# SLIM-DDS-107.net
KiCad netlist of a schematic drawn in EAGLE
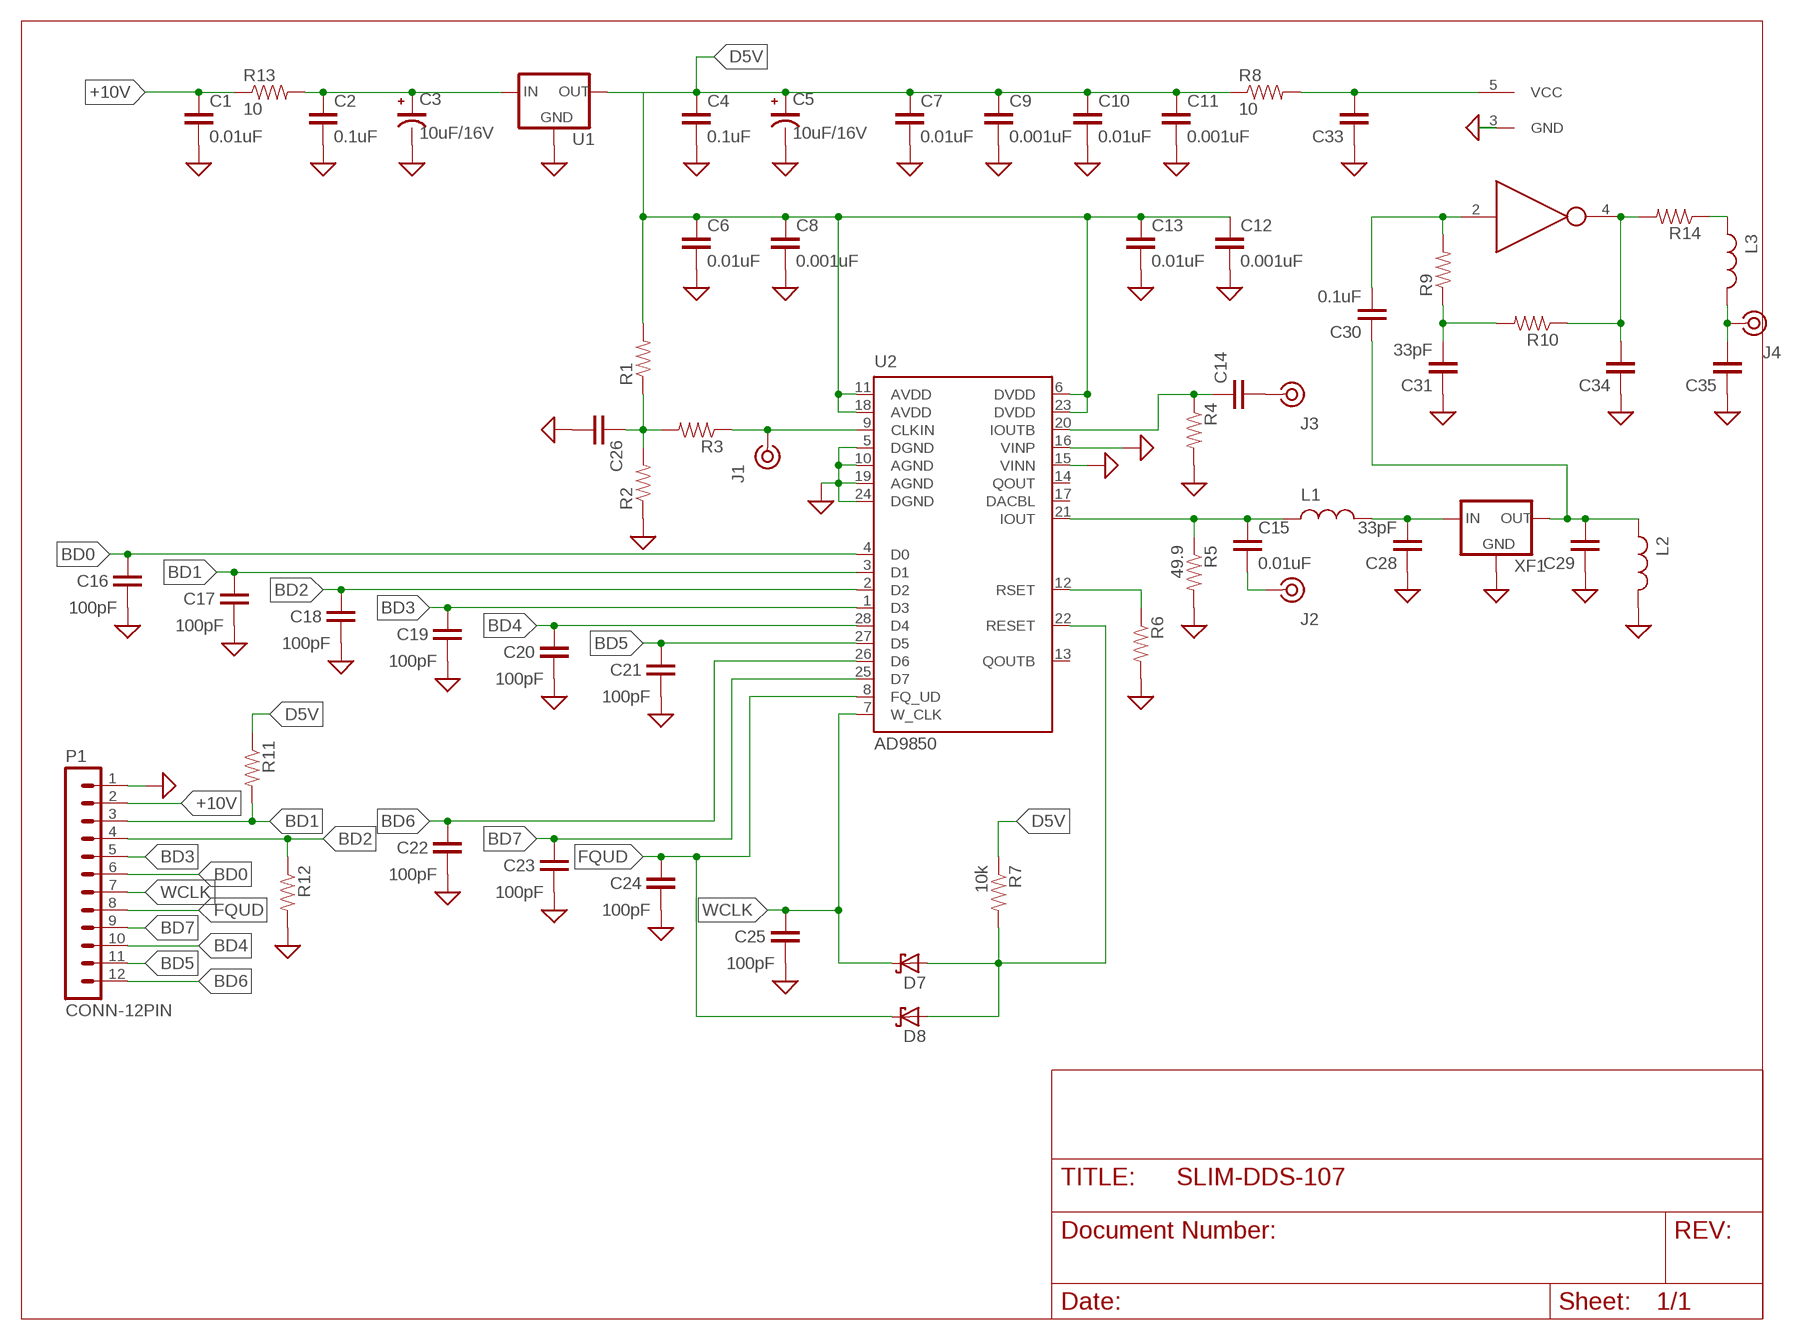
[diagram p0: schematic, sheet 1]

(export (version "E")
  (design (tool "Eeschema 10.0.6"))
  (components
    (comp (ref "C1")
      (value "0.01uF")
      (footprint "eagle-import:0805")
      (libsource (lib "eagle-import") (part "CAP0805"))
    )
    (comp (ref "C2")
      (value "0.1uF")
      (footprint "eagle-import:0805")
      (libsource (lib "eagle-import") (part "CAP0805"))
    )
    (comp (ref "C3")
      (value "10uF/16V")
      (footprint "eagle-import:EIA3216")
      (libsource (lib "eagle-import") (part "CAP-POL1206"))
    )
    (comp (ref "C4")
      (value "0.1uF")
      (footprint "eagle-import:0805")
      (libsource (lib "eagle-import") (part "CAP0805"))
    )
    (comp (ref "C5")
      (value "10uF/16V")
      (footprint "eagle-import:EIA3216")
      (libsource (lib "eagle-import") (part "CAP-POL1206"))
    )
    (comp (ref "C6")
      (value "0.01uF")
      (footprint "eagle-import:0805")
      (libsource (lib "eagle-import") (part "CAP0805"))
    )
    (comp (ref "C7")
      (value "0.01uF")
      (footprint "eagle-import:0805")
      (libsource (lib "eagle-import") (part "CAP0805"))
    )
    (comp (ref "C8")
      (value "0.001uF")
      (footprint "eagle-import:0805")
      (libsource (lib "eagle-import") (part "CAP0805"))
    )
    (comp (ref "C9")
      (value "0.001uF")
      (footprint "eagle-import:0805")
      (libsource (lib "eagle-import") (part "CAP0805"))
    )
    (comp (ref "C10")
      (value "0.01uF")
      (footprint "eagle-import:0805")
      (libsource (lib "eagle-import") (part "CAP0805"))
    )
    (comp (ref "C11")
      (value "0.001uF")
      (footprint "eagle-import:0805")
      (libsource (lib "eagle-import") (part "CAP0805"))
    )
    (comp (ref "C12")
      (value "0.001uF")
      (footprint "eagle-import:0805")
      (libsource (lib "eagle-import") (part "CAP0805"))
    )
    (comp (ref "C13")
      (value "0.01uF")
      (footprint "eagle-import:0805")
      (libsource (lib "eagle-import") (part "CAP0805"))
    )
    (comp (ref "C14")
      (value "CAP0805")
      (footprint "eagle-import:0805")
      (libsource (lib "eagle-import") (part "CAP0805"))
    )
    (comp (ref "C15")
      (value "0.01uF")
      (footprint "eagle-import:0805")
      (libsource (lib "eagle-import") (part "CAP0805"))
    )
    (comp (ref "C16")
      (value "100pF")
      (footprint "eagle-import:0805")
      (libsource (lib "eagle-import") (part "CAP0805"))
    )
    (comp (ref "C17")
      (value "100pF")
      (footprint "eagle-import:0805")
      (libsource (lib "eagle-import") (part "CAP0805"))
    )
    (comp (ref "C18")
      (value "100pF")
      (footprint "eagle-import:0805")
      (libsource (lib "eagle-import") (part "CAP0805"))
    )
    (comp (ref "C19")
      (value "100pF")
      (footprint "eagle-import:0805")
      (libsource (lib "eagle-import") (part "CAP0805"))
    )
    (comp (ref "C20")
      (value "100pF")
      (footprint "eagle-import:0805")
      (libsource (lib "eagle-import") (part "CAP0805"))
    )
    (comp (ref "C21")
      (value "100pF")
      (footprint "eagle-import:0805")
      (libsource (lib "eagle-import") (part "CAP0805"))
    )
    (comp (ref "C22")
      (value "100pF")
      (footprint "eagle-import:0805")
      (libsource (lib "eagle-import") (part "CAP0805"))
    )
    (comp (ref "C23")
      (value "100pF")
      (footprint "eagle-import:0805")
      (libsource (lib "eagle-import") (part "CAP0805"))
    )
    (comp (ref "C24")
      (value "100pF")
      (footprint "eagle-import:0805")
      (libsource (lib "eagle-import") (part "CAP0805"))
    )
    (comp (ref "C25")
      (value "100pF")
      (footprint "eagle-import:0805")
      (libsource (lib "eagle-import") (part "CAP0805"))
    )
    (comp (ref "C26")
      (value "CAP0805")
      (footprint "eagle-import:0805")
      (libsource (lib "eagle-import") (part "CAP0805"))
    )
    (comp (ref "C28")
      (value "33pF")
      (footprint "eagle-import:0805")
      (libsource (lib "eagle-import") (part "CAP0805"))
    )
    (comp (ref "C29")
      (value "CAP0805")
      (footprint "eagle-import:0805")
      (libsource (lib "eagle-import") (part "CAP0805"))
    )
    (comp (ref "C30")
      (value "0.1uF")
      (footprint "eagle-import:0805")
      (libsource (lib "eagle-import") (part "CAP0805"))
    )
    (comp (ref "C31")
      (value "33pF")
      (footprint "eagle-import:0805")
      (libsource (lib "eagle-import") (part "CAP0805"))
    )
    (comp (ref "C33")
      (value "CAP0805")
      (footprint "eagle-import:0805")
      (libsource (lib "eagle-import") (part "CAP0805"))
    )
    (comp (ref "C34")
      (value "CAP0805")
      (footprint "eagle-import:0805")
      (libsource (lib "eagle-import") (part "CAP0805"))
    )
    (comp (ref "C35")
      (value "CAP0805")
      (footprint "eagle-import:0805")
      (libsource (lib "eagle-import") (part "CAP0805"))
    )
    (comp (ref "D7")
      (value "SCHOTTKY-DIODE-SOD323")
      (footprint "eagle-import:SOD323")
      (libsource (lib "eagle-import") (part "SCHOTTKY-DIODE-SOD323"))
    )
    (comp (ref "D8")
      (value "SCHOTTKY-DIODE-SOD323")
      (footprint "eagle-import:SOD323")
      (libsource (lib "eagle-import") (part "SCHOTTKY-DIODE-SOD323"))
    )
    (comp (ref "J1")
      (value "COAX")
      (footprint "eagle-import:SLIM_COAX_PAD")
      (libsource (lib "eagle-import") (part "COAX"))
    )
    (comp (ref "J2")
      (value "COAX")
      (footprint "eagle-import:SLIM_COAX_PAD")
      (libsource (lib "eagle-import") (part "COAX"))
    )
    (comp (ref "J3")
      (value "COAX")
      (footprint "eagle-import:SLIM_COAX_PAD")
      (libsource (lib "eagle-import") (part "COAX"))
    )
    (comp (ref "J4")
      (value "COAX")
      (footprint "eagle-import:SLIM_COAX_PAD")
      (libsource (lib "eagle-import") (part "COAX"))
    )
    (comp (ref "L1")
      (value "INDUCTOR0805")
      (footprint "eagle-import:0805-IND")
      (libsource (lib "eagle-import") (part "INDUCTOR0805"))
    )
    (comp (ref "L2")
      (value "INDUCTOR0805")
      (footprint "eagle-import:0805-IND")
      (libsource (lib "eagle-import") (part "INDUCTOR0805"))
    )
    (comp (ref "L3")
      (value "INDUCTOR0805")
      (footprint "eagle-import:0805-IND")
      (libsource (lib "eagle-import") (part "INDUCTOR0805"))
    )
    (comp (ref "P1")
      (value "CONN-12PIN")
      (footprint "eagle-import:CONN-12PIN")
      (libsource (lib "eagle-import") (part "CONN-12PIN"))
    )
    (comp (ref "R1")
      (value "RESISTOR0805")
      (footprint "eagle-import:0805")
      (libsource (lib "eagle-import") (part "RESISTOR0805"))
    )
    (comp (ref "R2")
      (value "RESISTOR0805")
      (footprint "eagle-import:0805")
      (libsource (lib "eagle-import") (part "RESISTOR0805"))
    )
    (comp (ref "R3")
      (value "RESISTOR0805")
      (footprint "eagle-import:0805")
      (libsource (lib "eagle-import") (part "RESISTOR0805"))
    )
    (comp (ref "R4")
      (value "RESISTOR0805")
      (footprint "eagle-import:0805")
      (libsource (lib "eagle-import") (part "RESISTOR0805"))
    )
    (comp (ref "R5")
      (value "49.9")
      (footprint "eagle-import:0805")
      (libsource (lib "eagle-import") (part "RESISTOR0805"))
    )
    (comp (ref "R6")
      (value "RESISTOR0805")
      (footprint "eagle-import:0805")
      (libsource (lib "eagle-import") (part "RESISTOR0805"))
    )
    (comp (ref "R7")
      (value "10k")
      (footprint "eagle-import:0805")
      (libsource (lib "eagle-import") (part "RESISTOR0805"))
    )
    (comp (ref "R8")
      (value "10")
      (footprint "eagle-import:0805")
      (libsource (lib "eagle-import") (part "RESISTOR0805"))
    )
    (comp (ref "R9")
      (value "RESISTOR0805")
      (footprint "eagle-import:0805")
      (libsource (lib "eagle-import") (part "RESISTOR0805"))
    )
    (comp (ref "R10")
      (value "RESISTOR0805")
      (footprint "eagle-import:0805")
      (libsource (lib "eagle-import") (part "RESISTOR0805"))
    )
    (comp (ref "R11")
      (value "RESISTOR0805")
      (footprint "eagle-import:0805")
      (libsource (lib "eagle-import") (part "RESISTOR0805"))
    )
    (comp (ref "R12")
      (value "RESISTOR0805")
      (footprint "eagle-import:0805")
      (libsource (lib "eagle-import") (part "RESISTOR0805"))
    )
    (comp (ref "R13")
      (value "10")
      (footprint "eagle-import:0805")
      (libsource (lib "eagle-import") (part "RESISTOR0805"))
    )
    (comp (ref "R14")
      (value "RESISTOR0805")
      (footprint "eagle-import:0805")
      (libsource (lib "eagle-import") (part "RESISTOR0805"))
    )
    (comp (ref "U$1")
      (value "7SZ04SOT-23")
      (footprint "eagle-import:SOT23-5L")
      (libsource (lib "eagle-import") (part "7SZ04SOT-23"))
    )
    (comp (ref "U1")
      (value "78MXXLDPAK")
      (footprint "eagle-import:TO252")
      (libsource (lib "eagle-import") (part "78MXXLDPAK"))
    )
    (comp (ref "U2")
      (value "AD9850")
      (footprint "eagle-import:SSOP28")
      (libsource (lib "eagle-import") (part "AD9850"))
    )
    (comp (ref "XF1")
      (value "XTALFILTER")
      (footprint "eagle-import:XTALFILTER")
      (libsource (lib "eagle-import") (part "XTALFILTER"))
    )
  )
  (nets
    (net (code "1") (name "+10V") (class "Default")
      (node (ref "C1") (pin "1") (pinfunction "1_1") (pintype "passive"))
      (node (ref "P1") (pin "2") (pinfunction "2_2") (pintype "passive"))
      (node (ref "R13") (pin "1") (pinfunction "1_1") (pintype "passive"))
    )
    (net (code "2") (name "BD0") (class "Default")
      (node (ref "C16") (pin "2") (pinfunction "2_2") (pintype "passive"))
      (node (ref "P1") (pin "6") (pinfunction "6_6") (pintype "passive"))
      (node (ref "U2") (pin "4") (pinfunction "D0_4") (pintype "bidirectional"))
    )
    (net (code "3") (name "BD1") (class "Default")
      (node (ref "C17") (pin "2") (pinfunction "2_2") (pintype "passive"))
      (node (ref "P1") (pin "3") (pinfunction "3_3") (pintype "passive"))
      (node (ref "R11") (pin "2") (pinfunction "2_2") (pintype "passive"))
      (node (ref "U2") (pin "3") (pinfunction "D1_3") (pintype "bidirectional"))
    )
    (net (code "4") (name "BD2") (class "Default")
      (node (ref "C18") (pin "2") (pinfunction "2_2") (pintype "passive"))
      (node (ref "P1") (pin "4") (pinfunction "4_4") (pintype "passive"))
      (node (ref "R12") (pin "1") (pinfunction "1_1") (pintype "passive"))
      (node (ref "U2") (pin "2") (pinfunction "D2_2") (pintype "bidirectional"))
    )
    (net (code "5") (name "BD3") (class "Default")
      (node (ref "C19") (pin "2") (pinfunction "2_2") (pintype "passive"))
      (node (ref "P1") (pin "5") (pinfunction "5_5") (pintype "passive"))
      (node (ref "U2") (pin "1") (pinfunction "D3_1") (pintype "bidirectional"))
    )
    (net (code "6") (name "BD4") (class "Default")
      (node (ref "C20") (pin "2") (pinfunction "2_2") (pintype "passive"))
      (node (ref "P1") (pin "10") (pinfunction "10_10") (pintype "passive"))
      (node (ref "U2") (pin "28") (pinfunction "D4_28") (pintype "bidirectional"))
    )
    (net (code "7") (name "BD5") (class "Default")
      (node (ref "C21") (pin "2") (pinfunction "2_2") (pintype "passive"))
      (node (ref "P1") (pin "11") (pinfunction "11_11") (pintype "passive"))
      (node (ref "U2") (pin "27") (pinfunction "D5_27") (pintype "bidirectional"))
    )
    (net (code "8") (name "BD6") (class "Default")
      (node (ref "C22") (pin "2") (pinfunction "2_2") (pintype "passive"))
      (node (ref "P1") (pin "12") (pinfunction "12_12") (pintype "passive"))
      (node (ref "U2") (pin "26") (pinfunction "D6_26") (pintype "bidirectional"))
    )
    (net (code "9") (name "BD7") (class "Default")
      (node (ref "C23") (pin "2") (pinfunction "2_2") (pintype "passive"))
      (node (ref "P1") (pin "9") (pinfunction "9_9") (pintype "passive"))
      (node (ref "U2") (pin "25") (pinfunction "D7_25") (pintype "bidirectional"))
    )
    (net (code "10") (name "D5V") (class "Default")
      (node (ref "C10") (pin "1") (pinfunction "1_1") (pintype "passive"))
      (node (ref "C11") (pin "1") (pinfunction "1_1") (pintype "passive"))
      (node (ref "C12") (pin "1") (pinfunction "1_1") (pintype "passive"))
      (node (ref "C13") (pin "1") (pinfunction "1_1") (pintype "passive"))
      (node (ref "C4") (pin "1") (pinfunction "1_1") (pintype "passive"))
      (node (ref "C5") (pin "A") (pinfunction "+_A") (pintype "passive"))
      (node (ref "C6") (pin "1") (pinfunction "1_1") (pintype "passive"))
      (node (ref "C7") (pin "1") (pinfunction "1_1") (pintype "passive"))
      (node (ref "C8") (pin "1") (pinfunction "1_1") (pintype "passive"))
      (node (ref "C9") (pin "1") (pinfunction "1_1") (pintype "passive"))
      (node (ref "R1") (pin "2") (pinfunction "2_2") (pintype "passive"))
      (node (ref "R11") (pin "1") (pinfunction "1_1") (pintype "passive"))
      (node (ref "R7") (pin "1") (pinfunction "1_1") (pintype "passive"))
      (node (ref "R8") (pin "1") (pinfunction "1_1") (pintype "passive"))
      (node (ref "U1") (pin "2") (pinfunction "OUT_2") (pintype "passive"))
      (node (ref "U2") (pin "11") (pinfunction "AVDD_11") (pintype "bidirectional"))
      (node (ref "U2") (pin "18") (pinfunction "AVDD_18") (pintype "bidirectional"))
      (node (ref "U2") (pin "23") (pinfunction "DVDD_23") (pintype "bidirectional"))
      (node (ref "U2") (pin "6") (pinfunction "DVDD_6") (pintype "bidirectional"))
    )
    (net (code "11") (name "FQUD") (class "Default")
      (node (ref "C24") (pin "2") (pinfunction "2_2") (pintype "passive"))
      (node (ref "D8") (pin "C") (pinfunction "C_C") (pintype "passive"))
      (node (ref "P1") (pin "8") (pinfunction "8_8") (pintype "passive"))
      (node (ref "U2") (pin "8") (pinfunction "FQ_UD_8") (pintype "bidirectional"))
    )
    (net (code "12") (name "GND") (class "Default")
      (node (ref "C1") (pin "2") (pinfunction "2_2") (pintype "passive"))
      (node (ref "C10") (pin "2") (pinfunction "2_2") (pintype "passive"))
      (node (ref "C11") (pin "2") (pinfunction "2_2") (pintype "passive"))
      (node (ref "C12") (pin "2") (pinfunction "2_2") (pintype "passive"))
      (node (ref "C13") (pin "2") (pinfunction "2_2") (pintype "passive"))
      (node (ref "C16") (pin "1") (pinfunction "1_1") (pintype "passive"))
      (node (ref "C17") (pin "1") (pinfunction "1_1") (pintype "passive"))
      (node (ref "C18") (pin "1") (pinfunction "1_1") (pintype "passive"))
      (node (ref "C19") (pin "1") (pinfunction "1_1") (pintype "passive"))
      (node (ref "C2") (pin "2") (pinfunction "2_2") (pintype "passive"))
      (node (ref "C20") (pin "1") (pinfunction "1_1") (pintype "passive"))
      (node (ref "C21") (pin "1") (pinfunction "1_1") (pintype "passive"))
      (node (ref "C22") (pin "1") (pinfunction "1_1") (pintype "passive"))
      (node (ref "C23") (pin "1") (pinfunction "1_1") (pintype "passive"))
      (node (ref "C24") (pin "1") (pinfunction "1_1") (pintype "passive"))
      (node (ref "C25") (pin "1") (pinfunction "1_1") (pintype "passive"))
      (node (ref "C26") (pin "2") (pinfunction "2_2") (pintype "passive"))
      (node (ref "C28") (pin "1") (pinfunction "1_1") (pintype "passive"))
      (node (ref "C29") (pin "1") (pinfunction "1_1") (pintype "passive"))
      (node (ref "C3") (pin "C") (pinfunction "-_C") (pintype "passive"))
      (node (ref "C31") (pin "1") (pinfunction "1_1") (pintype "passive"))
      (node (ref "C33") (pin "1") (pinfunction "1_1") (pintype "passive"))
      (node (ref "C34") (pin "1") (pinfunction "1_1") (pintype "passive"))
      (node (ref "C35") (pin "1") (pinfunction "1_1") (pintype "passive"))
      (node (ref "C4") (pin "2") (pinfunction "2_2") (pintype "passive"))
      (node (ref "C5") (pin "C") (pinfunction "-_C") (pintype "passive"))
      (node (ref "C6") (pin "2") (pinfunction "2_2") (pintype "passive"))
      (node (ref "C7") (pin "2") (pinfunction "2_2") (pintype "passive"))
      (node (ref "C8") (pin "2") (pinfunction "2_2") (pintype "passive"))
      (node (ref "C9") (pin "2") (pinfunction "2_2") (pintype "passive"))
      (node (ref "L2") (pin "2") (pinfunction "P$2_2") (pintype "passive"))
      (node (ref "P1") (pin "1") (pinfunction "1_1") (pintype "passive"))
      (node (ref "R12") (pin "2") (pinfunction "2_2") (pintype "passive"))
      (node (ref "R2") (pin "1") (pinfunction "1_1") (pintype "passive"))
      (node (ref "R4") (pin "2") (pinfunction "2_2") (pintype "passive"))
      (node (ref "R5") (pin "2") (pinfunction "2_2") (pintype "passive"))
      (node (ref "R6") (pin "2") (pinfunction "2_2") (pintype "passive"))
      (node (ref "U$1") (pin "3") (pinfunction "GND_3") (pintype "bidirectional"))
      (node (ref "U1") (pin "3") (pinfunction "GND_3") (pintype "input"))
      (node (ref "U2") (pin "10") (pinfunction "AGND_10") (pintype "bidirectional"))
      (node (ref "U2") (pin "15") (pinfunction "VINN_15") (pintype "bidirectional"))
      (node (ref "U2") (pin "16") (pinfunction "VINP_16") (pintype "bidirectional"))
      (node (ref "U2") (pin "19") (pinfunction "AGND_19") (pintype "bidirectional"))
      (node (ref "U2") (pin "24") (pinfunction "DGND_24") (pintype "bidirectional"))
      (node (ref "U2") (pin "5") (pinfunction "DGND_5") (pintype "bidirectional"))
      (node (ref "XF1") (pin "3") (pinfunction "GND_3") (pintype "input"))
    )
    (net (code "13") (name "Net-(C3-+)") (class "Default")
      (node (ref "C2") (pin "1") (pinfunction "1_1") (pintype "passive"))
      (node (ref "C3") (pin "A") (pinfunction "+_A") (pintype "passive"))
      (node (ref "R13") (pin "2") (pinfunction "2_2") (pintype "passive"))
      (node (ref "U1") (pin "1") (pinfunction "IN_1") (pintype "input"))
    )
    (net (code "14") (name "Net-(C26-Pad1)") (class "Default")
      (node (ref "C26") (pin "1") (pinfunction "1_1") (pintype "passive"))
      (node (ref "R1") (pin "1") (pinfunction "1_1") (pintype "passive"))
      (node (ref "R2") (pin "2") (pinfunction "2_2") (pintype "passive"))
      (node (ref "R3") (pin "2") (pinfunction "2_2") (pintype "passive"))
    )
    (net (code "15") (name "Net-(C31-Pad2)") (class "Default")
      (node (ref "C31") (pin "2") (pinfunction "2_2") (pintype "passive"))
      (node (ref "R10") (pin "2") (pinfunction "2_2") (pintype "passive"))
      (node (ref "R9") (pin "1") (pinfunction "1_1") (pintype "passive"))
    )
    (net (code "16") (name "Net-(J1A-1)") (class "Default")
      (node (ref "J1") (pin "P$1") (pinfunction "1_P$1") (pintype "passive"))
      (node (ref "R3") (pin "1") (pinfunction "1_1") (pintype "passive"))
      (node (ref "U2") (pin "9") (pinfunction "CLKIN_9") (pintype "bidirectional"))
    )
    (net (code "17") (name "Net-(J2A-1)") (class "Default")
      (node (ref "C15") (pin "2") (pinfunction "2_2") (pintype "passive"))
      (node (ref "J2") (pin "P$1") (pinfunction "1_P$1") (pintype "passive"))
    )
    (net (code "18") (name "Net-(J3A-1)") (class "Default")
      (node (ref "C14") (pin "2") (pinfunction "2_2") (pintype "passive"))
      (node (ref "J3") (pin "P$1") (pinfunction "1_P$1") (pintype "passive"))
    )
    (net (code "19") (name "Net-(J4A-1)") (class "Default")
      (node (ref "C35") (pin "2") (pinfunction "2_2") (pintype "passive"))
      (node (ref "J4") (pin "P$1") (pinfunction "1_P$1") (pintype "passive"))
      (node (ref "L3") (pin "2") (pinfunction "P$2_2") (pintype "passive"))
    )
    (net (code "20") (name "Net-(L1-P$1)") (class "Default")
      (node (ref "C15") (pin "1") (pinfunction "1_1") (pintype "passive"))
      (node (ref "L1") (pin "1") (pinfunction "P$1_1") (pintype "passive"))
      (node (ref "R5") (pin "1") (pinfunction "1_1") (pintype "passive"))
      (node (ref "U2") (pin "21") (pinfunction "IOUT_21") (pintype "bidirectional"))
    )
    (net (code "21") (name "Net-(L1-P$2)") (class "Default")
      (node (ref "C28") (pin "2") (pinfunction "2_2") (pintype "passive"))
      (node (ref "L1") (pin "2") (pinfunction "P$2_2") (pintype "passive"))
      (node (ref "XF1") (pin "2") (pinfunction "IN_2") (pintype "input"))
    )
    (net (code "22") (name "Net-(L2-P$1)") (class "Default")
      (node (ref "C29") (pin "2") (pinfunction "2_2") (pintype "passive"))
      (node (ref "C30") (pin "1") (pinfunction "1_1") (pintype "passive"))
      (node (ref "L2") (pin "1") (pinfunction "P$1_1") (pintype "passive"))
      (node (ref "XF1") (pin "1") (pinfunction "OUT_1") (pintype "passive"))
    )
    (net (code "23") (name "Net-(L3-P$1)") (class "Default")
      (node (ref "L3") (pin "1") (pinfunction "P$1_1") (pintype "passive"))
      (node (ref "R14") (pin "1") (pinfunction "1_1") (pintype "passive"))
    )
    (net (code "24") (name "Net-(U$1A-IN)") (class "Default")
      (node (ref "C30") (pin "2") (pinfunction "2_2") (pintype "passive"))
      (node (ref "R9") (pin "2") (pinfunction "2_2") (pintype "passive"))
      (node (ref "U$1") (pin "2") (pinfunction "IN_2") (pintype "input"))
    )
    (net (code "25") (name "Net-(U$1A-OUT)") (class "Default")
      (node (ref "C34") (pin "2") (pinfunction "2_2") (pintype "passive"))
      (node (ref "R10") (pin "1") (pinfunction "1_1") (pintype "passive"))
      (node (ref "R14") (pin "2") (pinfunction "2_2") (pintype "passive"))
      (node (ref "U$1") (pin "4") (pinfunction "OUT_4") (pintype "output"))
    )
    (net (code "26") (name "Net-(U$1B-VCC)") (class "Default")
      (node (ref "C33") (pin "2") (pinfunction "2_2") (pintype "passive"))
      (node (ref "R8") (pin "2") (pinfunction "2_2") (pintype "passive"))
      (node (ref "U$1") (pin "5") (pinfunction "VCC_5") (pintype "bidirectional"))
    )
    (net (code "27") (name "Net-(U2-IOUTB)") (class "Default")
      (node (ref "C14") (pin "1") (pinfunction "1_1") (pintype "passive"))
      (node (ref "R4") (pin "1") (pinfunction "1_1") (pintype "passive"))
      (node (ref "U2") (pin "20") (pinfunction "IOUTB_20") (pintype "bidirectional"))
    )
    (net (code "28") (name "Net-(U2-RESET)") (class "Default")
      (node (ref "D7") (pin "A") (pinfunction "A_A") (pintype "passive"))
      (node (ref "D8") (pin "A") (pinfunction "A_A") (pintype "passive"))
      (node (ref "R7") (pin "2") (pinfunction "2_2") (pintype "passive"))
      (node (ref "U2") (pin "22") (pinfunction "RESET_22") (pintype "bidirectional"))
    )
    (net (code "29") (name "Net-(U2-RSET)") (class "Default")
      (node (ref "R6") (pin "1") (pinfunction "1_1") (pintype "passive"))
      (node (ref "U2") (pin "12") (pinfunction "RSET_12") (pintype "bidirectional"))
    )
    (net (code "30") (name "WCLK") (class "Default")
      (node (ref "C25") (pin "2") (pinfunction "2_2") (pintype "passive"))
      (node (ref "D7") (pin "C") (pinfunction "C_C") (pintype "passive"))
      (node (ref "P1") (pin "7") (pinfunction "7_7") (pintype "passive"))
      (node (ref "U2") (pin "7") (pinfunction "W_CLK_7") (pintype "bidirectional"))
    )
    (net (code "31") (name "unconnected-(U2-DACBL-Pad17)") (class "Default")
      (node (ref "U2") (pin "17") (pinfunction "DACBL_17") (pintype "bidirectional"))
    )
    (net (code "32") (name "unconnected-(U2-QOUT-Pad14)") (class "Default")
      (node (ref "U2") (pin "14") (pinfunction "QOUT_14") (pintype "bidirectional"))
    )
    (net (code "33") (name "unconnected-(U2-QOUTB-Pad13)") (class "Default")
      (node (ref "U2") (pin "13") (pinfunction "QOUTB_13") (pintype "bidirectional"))
    )
  )
)
